# RoboBee_keypad.net
KiCad netlist of a schematic drawn in EAGLE
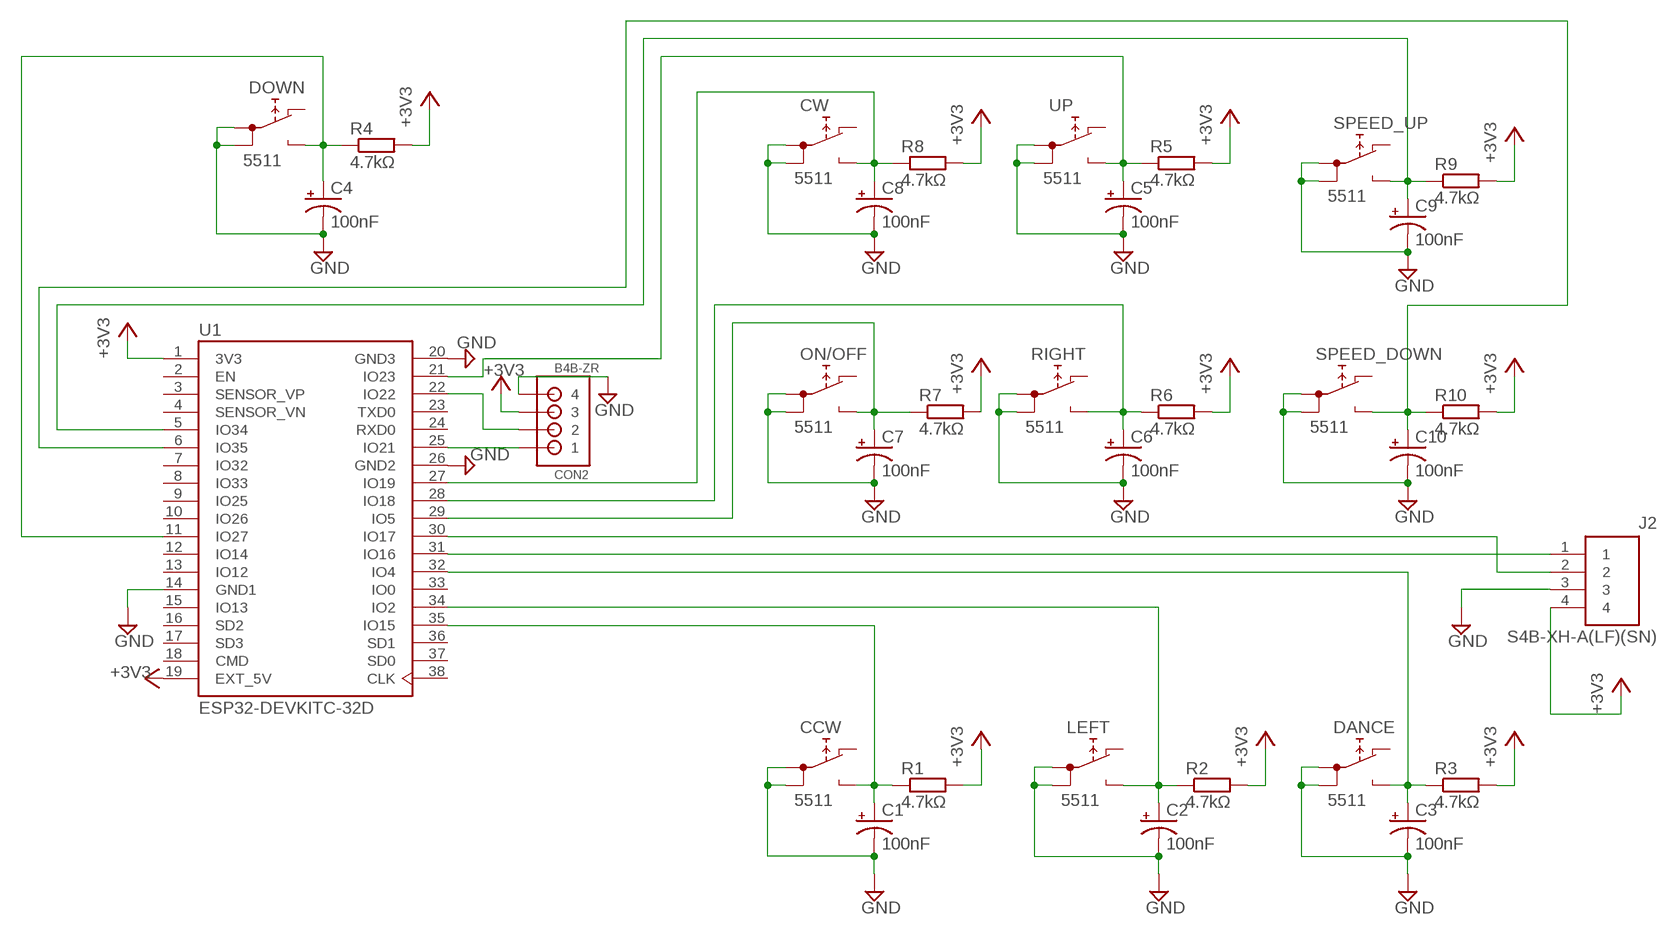
[diagram p0: schematic, sheet 1]

(export (version "E")
  (design (tool "Eeschema 10.0.6"))
  (components
    (comp (ref "C1")
      (value "100nF")
      (footprint "eagle-import:E1,8-4")
      (libsource (lib "eagle-import") (part "CPOL-USE1.8-4"))
    )
    (comp (ref "C2")
      (value "100nF")
      (footprint "eagle-import:E1,8-4")
      (libsource (lib "eagle-import") (part "CPOL-USE1.8-4"))
    )
    (comp (ref "C3")
      (value "100nF")
      (footprint "eagle-import:E1,8-4")
      (libsource (lib "eagle-import") (part "CPOL-USE1.8-4"))
    )
    (comp (ref "C4")
      (value "100nF")
      (footprint "eagle-import:E1,8-4")
      (libsource (lib "eagle-import") (part "CPOL-USE1.8-4"))
    )
    (comp (ref "C5")
      (value "100nF")
      (footprint "eagle-import:E1,8-4")
      (libsource (lib "eagle-import") (part "CPOL-USE1.8-4"))
    )
    (comp (ref "C6")
      (value "100nF")
      (footprint "eagle-import:E1,8-4")
      (libsource (lib "eagle-import") (part "CPOL-USE1.8-4"))
    )
    (comp (ref "C7")
      (value "100nF")
      (footprint "eagle-import:E1,8-4")
      (libsource (lib "eagle-import") (part "CPOL-USE1.8-4"))
    )
    (comp (ref "C8")
      (value "100nF")
      (footprint "eagle-import:E1,8-4")
      (libsource (lib "eagle-import") (part "CPOL-USE1.8-4"))
    )
    (comp (ref "C9")
      (value "100nF")
      (footprint "eagle-import:E1,8-4")
      (libsource (lib "eagle-import") (part "CPOL-USE1.8-4"))
    )
    (comp (ref "C10")
      (value "100nF")
      (footprint "eagle-import:E1,8-4")
      (libsource (lib "eagle-import") (part "CPOL-USE1.8-4"))
    )
    (comp (ref "CCW")
      (value "5511")
      (footprint "eagle-import:5511")
      (libsource (lib "eagle-import") (part "55?11"))
    )
    (comp (ref "CON2")
      (value "B4B-ZR")
      (footprint "eagle-import:B4B-ZR")
      (libsource (lib "eagle-import") (part "B4B-ZR"))
    )
    (comp (ref "CW")
      (value "5511")
      (footprint "eagle-import:5511")
      (libsource (lib "eagle-import") (part "55?11"))
    )
    (comp (ref "DANCE")
      (value "5511")
      (footprint "eagle-import:5511")
      (libsource (lib "eagle-import") (part "55?11"))
    )
    (comp (ref "DOWN")
      (value "5511")
      (footprint "eagle-import:5511")
      (libsource (lib "eagle-import") (part "55?11"))
    )
    (comp (ref "J2")
      (value "S4B-XH-A(LF)(SN)")
      (footprint "eagle-import:HDR-04_RA")
      (fields
        (field (name "DIGIKEY_PART_NUMBER") "455-2243-ND")
        (field (name "MANUFACTURER") "JST Sales America Inc.")
        (field (name "CREATED_BY") "PCBLayout.com")
      )
      (libsource (lib "eagle-import") (part "S4B-XH-A(LF)(SN)"))
    )
    (comp (ref "LEFT")
      (value "5511")
      (footprint "eagle-import:5511")
      (libsource (lib "eagle-import") (part "55?11"))
    )
    (comp (ref "ON/OFF")
      (value "5511")
      (footprint "eagle-import:5511")
      (libsource (lib "eagle-import") (part "55?11"))
    )
    (comp (ref "R1")
      (value "4.7kΩ")
      (footprint "eagle-import:0207_10")
      (libsource (lib "eagle-import") (part "R-EU_0207/10"))
    )
    (comp (ref "R2")
      (value "4.7kΩ")
      (footprint "eagle-import:0207_10")
      (libsource (lib "eagle-import") (part "R-EU_0207/10"))
    )
    (comp (ref "R3")
      (value "4.7kΩ")
      (footprint "eagle-import:0207_10")
      (libsource (lib "eagle-import") (part "R-EU_0207/10"))
    )
    (comp (ref "R4")
      (value "4.7kΩ")
      (footprint "eagle-import:0207_10")
      (libsource (lib "eagle-import") (part "R-EU_0207/10"))
    )
    (comp (ref "R5")
      (value "4.7kΩ")
      (footprint "eagle-import:0207_10")
      (libsource (lib "eagle-import") (part "R-EU_0207/10"))
    )
    (comp (ref "R6")
      (value "4.7kΩ")
      (footprint "eagle-import:0207_10")
      (libsource (lib "eagle-import") (part "R-EU_0207/10"))
    )
    (comp (ref "R7")
      (value "4.7kΩ")
      (footprint "eagle-import:0207_10")
      (libsource (lib "eagle-import") (part "R-EU_0207/10"))
    )
    (comp (ref "R8")
      (value "4.7kΩ")
      (footprint "eagle-import:0207_10")
      (libsource (lib "eagle-import") (part "R-EU_0207/10"))
    )
    (comp (ref "R9")
      (value "4.7kΩ")
      (footprint "eagle-import:0207_10")
      (libsource (lib "eagle-import") (part "R-EU_0207/10"))
    )
    (comp (ref "R10")
      (value "4.7kΩ")
      (footprint "eagle-import:0207_10")
      (libsource (lib "eagle-import") (part "R-EU_0207/10"))
    )
    (comp (ref "RIGHT")
      (value "5511")
      (footprint "eagle-import:5511")
      (libsource (lib "eagle-import") (part "55?11"))
    )
    (comp (ref "SPEED_DOWN")
      (value "5511")
      (footprint "eagle-import:5511")
      (libsource (lib "eagle-import") (part "55?11"))
    )
    (comp (ref "SPEED_UP")
      (value "5511")
      (footprint "eagle-import:5511")
      (libsource (lib "eagle-import") (part "55?11"))
    )
    (comp (ref "U1")
      (value "ESP32-DEVKITC-32D")
      (footprint "eagle-import:MODULE_ESP32-DEVKITC-32D")
      (fields (field (name "MF") "Espressif Systems"))
      (libsource (lib "eagle-import") (part "ESP32-DEVKITC-32D"))
    )
    (comp (ref "UP")
      (value "5511")
      (footprint "eagle-import:5511")
      (libsource (lib "eagle-import") (part "55?11"))
    )
  )
  (nets
    (net (code "1") (name "+3V3") (class "Default")
      (node (ref "CON2") (pin "3") (pinfunction "3_3") (pintype "bidirectional"))
      (node (ref "J2") (pin "4") (pinfunction "4_4") (pintype "passive"))
      (node (ref "R1") (pin "2") (pinfunction "2_2") (pintype "passive"))
      (node (ref "R10") (pin "2") (pinfunction "2_2") (pintype "passive"))
      (node (ref "R2") (pin "2") (pinfunction "2_2") (pintype "passive"))
      (node (ref "R3") (pin "2") (pinfunction "2_2") (pintype "passive"))
      (node (ref "R4") (pin "2") (pinfunction "2_2") (pintype "passive"))
      (node (ref "R5") (pin "2") (pinfunction "2_2") (pintype "passive"))
      (node (ref "R6") (pin "2") (pinfunction "2_2") (pintype "passive"))
      (node (ref "R7") (pin "2") (pinfunction "2_2") (pintype "passive"))
      (node (ref "R8") (pin "2") (pinfunction "2_2") (pintype "passive"))
      (node (ref "R9") (pin "2") (pinfunction "2_2") (pintype "passive"))
      (node (ref "U1") (pin "1") (pinfunction "3V3_1") (pintype "power_in"))
      (node (ref "U1") (pin "19") (pinfunction "EXT_5V_19") (pintype "power_in"))
    )
    (net (code "2") (name "GND") (class "Default")
      (node (ref "C1") (pin "-") (pinfunction "-_-") (pintype "passive"))
      (node (ref "C10") (pin "-") (pinfunction "-_-") (pintype "passive"))
      (node (ref "C2") (pin "-") (pinfunction "-_-") (pintype "passive"))
      (node (ref "C3") (pin "-") (pinfunction "-_-") (pintype "passive"))
      (node (ref "C4") (pin "-") (pinfunction "-_-") (pintype "passive"))
      (node (ref "C5") (pin "-") (pinfunction "-_-") (pintype "passive"))
      (node (ref "C6") (pin "-") (pinfunction "-_-") (pintype "passive"))
      (node (ref "C7") (pin "-") (pinfunction "-_-") (pintype "passive"))
      (node (ref "C8") (pin "-") (pinfunction "-_-") (pintype "passive"))
      (node (ref "C9") (pin "-") (pinfunction "-_-") (pintype "passive"))
      (node (ref "CCW") (pin "1A") (pinfunction "1A_1A") (pintype "passive"))
      (node (ref "CCW") (pin "1B") (pinfunction "1B_1B") (pintype "passive"))
      (node (ref "CON2") (pin "4") (pinfunction "4_4") (pintype "bidirectional"))
      (node (ref "CW") (pin "1A") (pinfunction "1A_1A") (pintype "passive"))
      (node (ref "CW") (pin "1B") (pinfunction "1B_1B") (pintype "passive"))
      (node (ref "DANCE") (pin "1A") (pinfunction "1A_1A") (pintype "passive"))
      (node (ref "DANCE") (pin "1B") (pinfunction "1B_1B") (pintype "passive"))
      (node (ref "DOWN") (pin "1A") (pinfunction "1A_1A") (pintype "passive"))
      (node (ref "DOWN") (pin "1B") (pinfunction "1B_1B") (pintype "passive"))
      (node (ref "J2") (pin "3") (pinfunction "3_3") (pintype "passive"))
      (node (ref "LEFT") (pin "1A") (pinfunction "1A_1A") (pintype "passive"))
      (node (ref "LEFT") (pin "1B") (pinfunction "1B_1B") (pintype "passive"))
      (node (ref "ON/OFF") (pin "1A") (pinfunction "1A_1A") (pintype "passive"))
      (node (ref "ON/OFF") (pin "1B") (pinfunction "1B_1B") (pintype "passive"))
      (node (ref "RIGHT") (pin "1A") (pinfunction "1A_1A") (pintype "passive"))
      (node (ref "RIGHT") (pin "1B") (pinfunction "1B_1B") (pintype "passive"))
      (node (ref "SPEED_DOWN") (pin "1A") (pinfunction "1A_1A") (pintype "passive"))
      (node (ref "SPEED_DOWN") (pin "1B") (pinfunction "1B_1B") (pintype "passive"))
      (node (ref "SPEED_UP") (pin "1A") (pinfunction "1A_1A") (pintype "passive"))
      (node (ref "SPEED_UP") (pin "1B") (pinfunction "1B_1B") (pintype "passive"))
      (node (ref "U1") (pin "14") (pinfunction "GND1_14") (pintype "power_in"))
      (node (ref "U1") (pin "20") (pinfunction "GND3_20") (pintype "power_in"))
      (node (ref "U1") (pin "26") (pinfunction "GND2_26") (pintype "power_in"))
      (node (ref "UP") (pin "1A") (pinfunction "1A_1A") (pintype "passive"))
      (node (ref "UP") (pin "1B") (pinfunction "1B_1B") (pintype "passive"))
    )
    (net (code "3") (name "Net-(U1-IO2)") (class "Default")
      (node (ref "C2") (pin "+") (pinfunction "+_+") (pintype "passive"))
      (node (ref "LEFT") (pin "NO") (pinfunction "NO_NO") (pintype "passive"))
      (node (ref "R2") (pin "1") (pinfunction "1_1") (pintype "passive"))
      (node (ref "U1") (pin "34") (pinfunction "IO2_34") (pintype "bidirectional"))
    )
    (net (code "4") (name "Net-(U1-IO4)") (class "Default")
      (node (ref "C3") (pin "+") (pinfunction "+_+") (pintype "passive"))
      (node (ref "DANCE") (pin "NO") (pinfunction "NO_NO") (pintype "passive"))
      (node (ref "R3") (pin "1") (pinfunction "1_1") (pintype "passive"))
      (node (ref "U1") (pin "32") (pinfunction "IO4_32") (pintype "bidirectional"))
    )
    (net (code "5") (name "Net-(U1-IO5)") (class "Default")
      (node (ref "C7") (pin "+") (pinfunction "+_+") (pintype "passive"))
      (node (ref "ON/OFF") (pin "NO") (pinfunction "NO_NO") (pintype "passive"))
      (node (ref "R7") (pin "1") (pinfunction "1_1") (pintype "passive"))
      (node (ref "U1") (pin "29") (pinfunction "IO5_29") (pintype "bidirectional"))
    )
    (net (code "6") (name "Net-(U1-IO15)") (class "Default")
      (node (ref "C1") (pin "+") (pinfunction "+_+") (pintype "passive"))
      (node (ref "CCW") (pin "NO") (pinfunction "NO_NO") (pintype "passive"))
      (node (ref "R1") (pin "1") (pinfunction "1_1") (pintype "passive"))
      (node (ref "U1") (pin "35") (pinfunction "IO15_35") (pintype "bidirectional"))
    )
    (net (code "7") (name "Net-(U1-IO16)") (class "Default")
      (node (ref "J2") (pin "1") (pinfunction "1_1") (pintype "passive"))
      (node (ref "U1") (pin "31") (pinfunction "IO16_31") (pintype "bidirectional"))
    )
    (net (code "8") (name "Net-(U1-IO17)") (class "Default")
      (node (ref "J2") (pin "2") (pinfunction "2_2") (pintype "passive"))
      (node (ref "U1") (pin "30") (pinfunction "IO17_30") (pintype "bidirectional"))
    )
    (net (code "9") (name "Net-(U1-IO18)") (class "Default")
      (node (ref "C6") (pin "+") (pinfunction "+_+") (pintype "passive"))
      (node (ref "R6") (pin "1") (pinfunction "1_1") (pintype "passive"))
      (node (ref "RIGHT") (pin "NO") (pinfunction "NO_NO") (pintype "passive"))
      (node (ref "U1") (pin "28") (pinfunction "IO18_28") (pintype "bidirectional"))
    )
    (net (code "10") (name "Net-(U1-IO19)") (class "Default")
      (node (ref "C8") (pin "+") (pinfunction "+_+") (pintype "passive"))
      (node (ref "CW") (pin "NO") (pinfunction "NO_NO") (pintype "passive"))
      (node (ref "R8") (pin "1") (pinfunction "1_1") (pintype "passive"))
      (node (ref "U1") (pin "27") (pinfunction "IO19_27") (pintype "bidirectional"))
    )
    (net (code "11") (name "Net-(U1-IO21)") (class "Default")
      (node (ref "CON2") (pin "1") (pinfunction "1_1") (pintype "bidirectional"))
      (node (ref "U1") (pin "25") (pinfunction "IO21_25") (pintype "bidirectional"))
    )
    (net (code "12") (name "Net-(U1-IO22)") (class "Default")
      (node (ref "CON2") (pin "2") (pinfunction "2_2") (pintype "bidirectional"))
      (node (ref "U1") (pin "22") (pinfunction "IO22_22") (pintype "bidirectional"))
    )
    (net (code "13") (name "Net-(U1-IO23)") (class "Default")
      (node (ref "C5") (pin "+") (pinfunction "+_+") (pintype "passive"))
      (node (ref "R5") (pin "1") (pinfunction "1_1") (pintype "passive"))
      (node (ref "U1") (pin "21") (pinfunction "IO23_21") (pintype "bidirectional"))
      (node (ref "UP") (pin "NO") (pinfunction "NO_NO") (pintype "passive"))
    )
    (net (code "14") (name "Net-(U1-IO27)") (class "Default")
      (node (ref "C4") (pin "+") (pinfunction "+_+") (pintype "passive"))
      (node (ref "DOWN") (pin "NO") (pinfunction "NO_NO") (pintype "passive"))
      (node (ref "R4") (pin "1") (pinfunction "1_1") (pintype "passive"))
      (node (ref "U1") (pin "11") (pinfunction "IO27_11") (pintype "bidirectional"))
    )
    (net (code "15") (name "Net-(U1-IO34)") (class "Default")
      (node (ref "C9") (pin "+") (pinfunction "+_+") (pintype "passive"))
      (node (ref "R9") (pin "1") (pinfunction "1_1") (pintype "passive"))
      (node (ref "SPEED_UP") (pin "NO") (pinfunction "NO_NO") (pintype "passive"))
      (node (ref "U1") (pin "5") (pinfunction "IO34_5") (pintype "bidirectional"))
    )
    (net (code "16") (name "Net-(U1-IO35)") (class "Default")
      (node (ref "C10") (pin "+") (pinfunction "+_+") (pintype "passive"))
      (node (ref "R10") (pin "1") (pinfunction "1_1") (pintype "passive"))
      (node (ref "SPEED_DOWN") (pin "NO") (pinfunction "NO_NO") (pintype "passive"))
      (node (ref "U1") (pin "6") (pinfunction "IO35_6") (pintype "bidirectional"))
    )
    (net (code "17") (name "unconnected-(CCW-PadNC)") (class "Default")
      (node (ref "CCW") (pin "NC") (pinfunction "NC_NC") (pintype "passive"))
    )
    (net (code "18") (name "unconnected-(CW-PadNC)") (class "Default")
      (node (ref "CW") (pin "NC") (pinfunction "NC_NC") (pintype "passive"))
    )
    (net (code "19") (name "unconnected-(DANCE-PadNC)") (class "Default")
      (node (ref "DANCE") (pin "NC") (pinfunction "NC_NC") (pintype "passive"))
    )
    (net (code "20") (name "unconnected-(DOWN-PadNC)") (class "Default")
      (node (ref "DOWN") (pin "NC") (pinfunction "NC_NC") (pintype "passive"))
    )
    (net (code "21") (name "unconnected-(LEFT-PadNC)") (class "Default")
      (node (ref "LEFT") (pin "NC") (pinfunction "NC_NC") (pintype "passive"))
    )
    (net (code "22") (name "unconnected-(ON/OFF-PadNC)") (class "Default")
      (node (ref "ON/OFF") (pin "NC") (pinfunction "NC_NC") (pintype "passive"))
    )
    (net (code "23") (name "unconnected-(RIGHT-PadNC)") (class "Default")
      (node (ref "RIGHT") (pin "NC") (pinfunction "NC_NC") (pintype "passive"))
    )
    (net (code "24") (name "unconnected-(SPEED_DOWN-PadNC)") (class "Default")
      (node (ref "SPEED_DOWN") (pin "NC") (pinfunction "NC_NC") (pintype "passive"))
    )
    (net (code "25") (name "unconnected-(SPEED_UP-PadNC)") (class "Default")
      (node (ref "SPEED_UP") (pin "NC") (pinfunction "NC_NC") (pintype "passive"))
    )
    (net (code "26") (name "unconnected-(U1-CLK-Pad38)") (class "Default")
      (node (ref "U1") (pin "38") (pinfunction "CLK_38") (pintype "input"))
    )
    (net (code "27") (name "unconnected-(U1-CMD-Pad18)") (class "Default")
      (node (ref "U1") (pin "18") (pinfunction "CMD_18") (pintype "bidirectional"))
    )
    (net (code "28") (name "unconnected-(U1-EN-Pad2)") (class "Default")
      (node (ref "U1") (pin "2") (pinfunction "EN_2") (pintype "input"))
    )
    (net (code "29") (name "unconnected-(U1-IO0-Pad33)") (class "Default")
      (node (ref "U1") (pin "33") (pinfunction "IO0_33") (pintype "bidirectional"))
    )
    (net (code "30") (name "unconnected-(U1-IO12-Pad13)") (class "Default")
      (node (ref "U1") (pin "13") (pinfunction "IO12_13") (pintype "bidirectional"))
    )
    (net (code "31") (name "unconnected-(U1-IO13-Pad15)") (class "Default")
      (node (ref "U1") (pin "15") (pinfunction "IO13_15") (pintype "bidirectional"))
    )
    (net (code "32") (name "unconnected-(U1-IO14-Pad12)") (class "Default")
      (node (ref "U1") (pin "12") (pinfunction "IO14_12") (pintype "bidirectional"))
    )
    (net (code "33") (name "unconnected-(U1-IO25-Pad9)") (class "Default")
      (node (ref "U1") (pin "9") (pinfunction "IO25_9") (pintype "bidirectional"))
    )
    (net (code "34") (name "unconnected-(U1-IO26-Pad10)") (class "Default")
      (node (ref "U1") (pin "10") (pinfunction "IO26_10") (pintype "bidirectional"))
    )
    (net (code "35") (name "unconnected-(U1-IO32-Pad7)") (class "Default")
      (node (ref "U1") (pin "7") (pinfunction "IO32_7") (pintype "bidirectional"))
    )
    (net (code "36") (name "unconnected-(U1-IO33-Pad8)") (class "Default")
      (node (ref "U1") (pin "8") (pinfunction "IO33_8") (pintype "bidirectional"))
    )
    (net (code "37") (name "unconnected-(U1-RXD0-Pad24)") (class "Default")
      (node (ref "U1") (pin "24") (pinfunction "RXD0_24") (pintype "input"))
    )
    (net (code "38") (name "unconnected-(U1-SD0-Pad37)") (class "Default")
      (node (ref "U1") (pin "37") (pinfunction "SD0_37") (pintype "bidirectional"))
    )
    (net (code "39") (name "unconnected-(U1-SD1-Pad36)") (class "Default")
      (node (ref "U1") (pin "36") (pinfunction "SD1_36") (pintype "bidirectional"))
    )
    (net (code "40") (name "unconnected-(U1-SD2-Pad16)") (class "Default")
      (node (ref "U1") (pin "16") (pinfunction "SD2_16") (pintype "bidirectional"))
    )
    (net (code "41") (name "unconnected-(U1-SD3-Pad17)") (class "Default")
      (node (ref "U1") (pin "17") (pinfunction "SD3_17") (pintype "bidirectional"))
    )
    (net (code "42") (name "unconnected-(U1-SENSOR_VN-Pad4)") (class "Default")
      (node (ref "U1") (pin "4") (pinfunction "SENSOR_VN_4") (pintype "input"))
    )
    (net (code "43") (name "unconnected-(U1-SENSOR_VP-Pad3)") (class "Default")
      (node (ref "U1") (pin "3") (pinfunction "SENSOR_VP_3") (pintype "input"))
    )
    (net (code "44") (name "unconnected-(U1-TXD0-Pad23)") (class "Default")
      (node (ref "U1") (pin "23") (pinfunction "TXD0_23") (pintype "output"))
    )
    (net (code "45") (name "unconnected-(UP-PadNC)") (class "Default")
      (node (ref "UP") (pin "NC") (pinfunction "NC_NC") (pintype "passive"))
    )
  )
)
